# signal_conditioning_circuit.net
KiCad netlist of a schematic drawn in Altium Designer
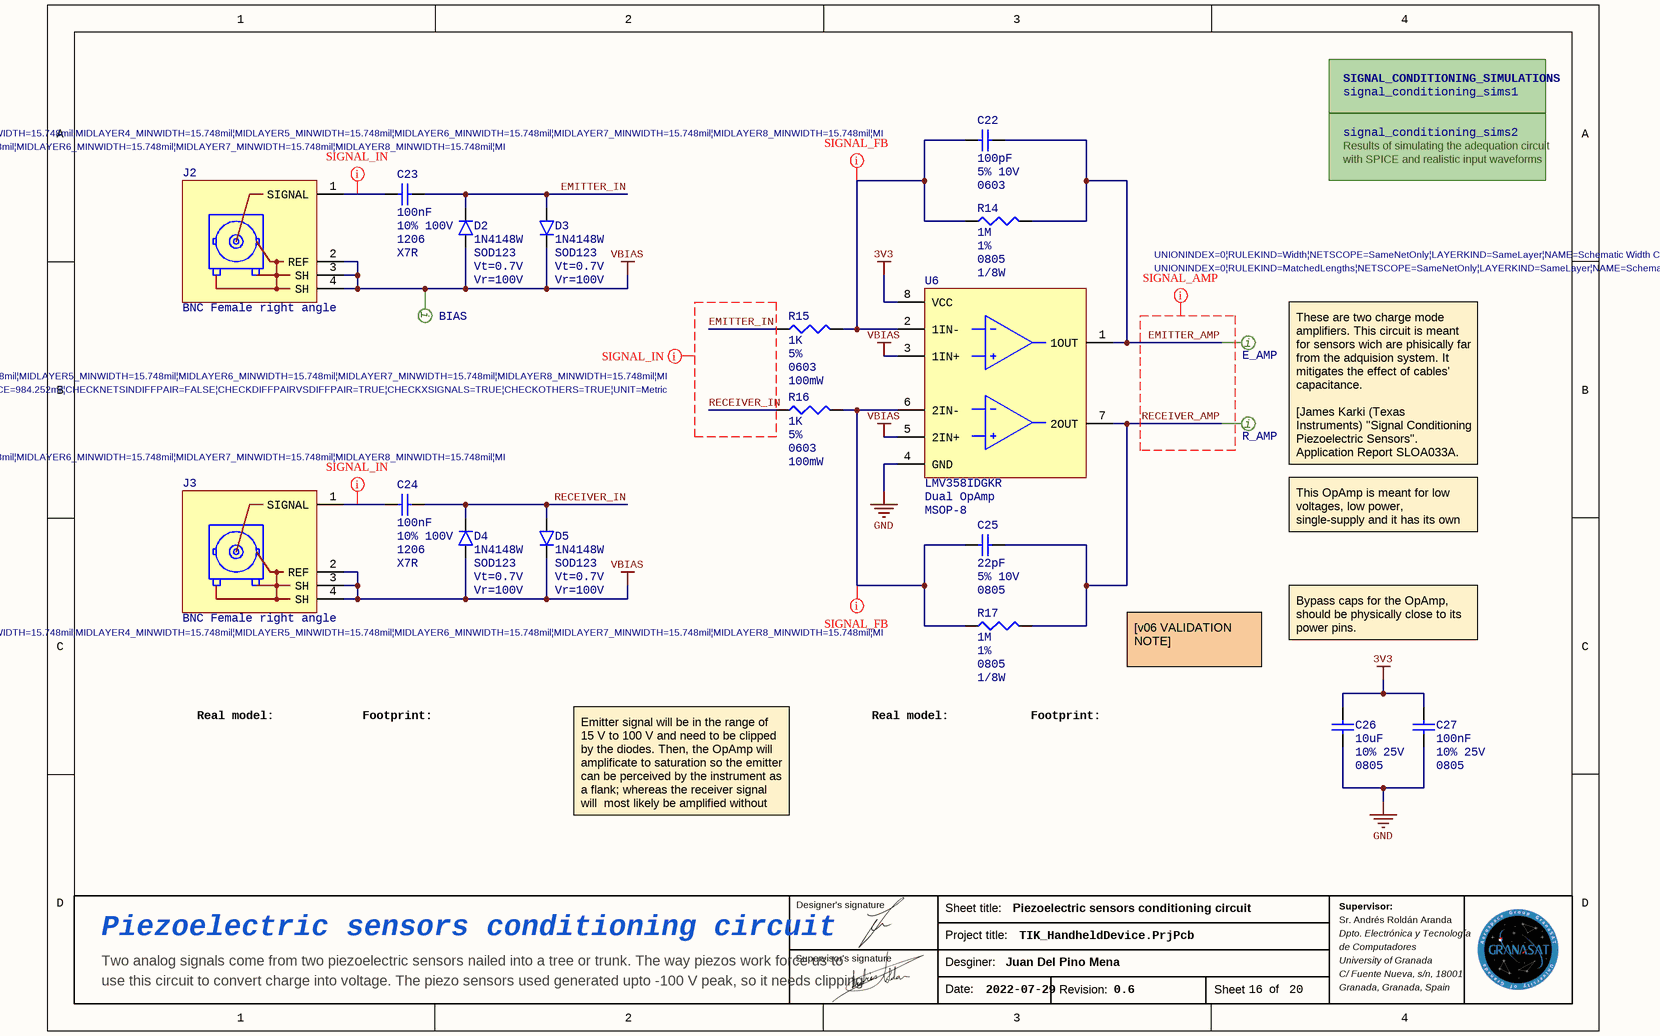
[diagram p0: signal_conditioning_circuit.SchDoc]

(export (version "E")
  (design (tool "Eeschema 10.0.6"))
  (components
    (comp (ref "BIAS")
      (value "Test Point Pad dual sided")
      (footprint "TEST POINT PAD")
      (description "Test point - PCB Pad dual sided")
      (libsource (lib "tik_handheld_schlib") (part "Test Point Pad dual sided"))
    )
    (comp (ref "C22")
      (value "100pF")
      (footprint "CAP 0603_1608")
      (description "Ceramic cap size 0805")
      (fields
        (field (name "TOLERANCE") "5% 10V")
        (field (name "PACKAGEDESCRIPTION") "0603")
        (field (name "Comment") "Cap_cer_0603_100pF_5%")
      )
      (libsource (lib "tik_handheld_schlib") (part "Cap_cer_0603_100pF_5%"))
    )
    (comp (ref "C23")
      (value "100nF")
      (footprint "CAP 1206_3216")
      (description "Ceramic cap size 1206 C1206C104K1RACTU")
      (fields
        (field (name "TOLERANCE") "10% 100V")
        (field (name "PACKAGEDESCRIPTION") "1206")
        (field (name "TYPE") "X7R")
        (field (name "Comment") "Cap_cer_0805")
      )
      (libsource (lib "tik_handheld_schlib") (part "Cap_cer_1206_100nF_100V_10%"))
    )
    (comp (ref "C24")
      (value "100nF")
      (footprint "CAP 1206_3216")
      (description "Ceramic cap size 1206 C1206C104K1RACTU")
      (fields
        (field (name "TOLERANCE") "10% 100V")
        (field (name "PACKAGEDESCRIPTION") "1206")
        (field (name "TYPE") "X7R")
        (field (name "Comment") "Cap_cer_0805")
      )
      (libsource (lib "tik_handheld_schlib") (part "Cap_cer_1206_100nF_100V_10%"))
    )
    (comp (ref "C25")
      (value "22pF")
      (footprint "CAP 0603_1608")
      (description "Ceramic cap size 0805")
      (fields
        (field (name "TOLERANCE") "5% 10V")
        (field (name "PACKAGEDESCRIPTION") "0805")
        (field (name "Comment") "Cap_cer_0603_22pF_5%")
      )
      (libsource (lib "tik_handheld_schlib") (part "Cap_cer_0603_22pF_5%"))
    )
    (comp (ref "C26")
      (value "10uF")
      (footprint "CAP 0805_2012")
      (description "Ceramic cap size 0805")
      (fields
        (field (name "TOLERANCE") "10% 25V")
        (field (name "PACKAGEDESCRIPTION") "0805")
        (field (name "Comment") "Cap_cer_0805")
      )
      (libsource (lib "tik_handheld_schlib") (part "Cap_cer_0805_10uF_10%"))
    )
    (comp (ref "C27")
      (value "100nF")
      (footprint "CAP 0805_2012")
      (description "Ceramic cap size 0805")
      (fields
        (field (name "TOLERANCE") "10% 25V")
        (field (name "PACKAGEDESCRIPTION") "0805")
        (field (name "Comment") "Cap_cer_0805")
      )
      (libsource (lib "tik_handheld_schlib") (part "Cap_cer_0805_100nF_10%"))
    )
    (comp (ref "D2")
      (value "Diode 1N4148W")
      (footprint "SOD123F 1N4148W")
      (description "SURFACE MOUNT FAST SWITCHING DIODE")
      (fields
        (field (name "PART") "1N4148W")
        (field (name "PACKAGEDESCRIPTION") "SOD123")
        (field (name "FORWARDVOLTAGE") "Vt=0.7V")
        (field (name "REVERSEVOLTAGE") "Vr=100V")
      )
      (libsource (lib "tik_handheld_schlib") (part "Diode 1N4148W"))
    )
    (comp (ref "D3")
      (value "Diode 1N4148W")
      (footprint "SOD123F 1N4148W")
      (description "SURFACE MOUNT FAST SWITCHING DIODE")
      (fields
        (field (name "PART") "1N4148W")
        (field (name "PACKAGEDESCRIPTION") "SOD123")
        (field (name "FORWARDVOLTAGE") "Vt=0.7V")
        (field (name "REVERSEVOLTAGE") "Vr=100V")
      )
      (libsource (lib "tik_handheld_schlib") (part "Diode 1N4148W"))
    )
    (comp (ref "D4")
      (value "Diode 1N4148W")
      (footprint "SOD123F 1N4148W")
      (description "SURFACE MOUNT FAST SWITCHING DIODE")
      (fields
        (field (name "PART") "1N4148W")
        (field (name "PACKAGEDESCRIPTION") "SOD123")
        (field (name "FORWARDVOLTAGE") "Vt=0.7V")
        (field (name "REVERSEVOLTAGE") "Vr=100V")
      )
      (libsource (lib "tik_handheld_schlib") (part "Diode 1N4148W"))
    )
    (comp (ref "D5")
      (value "Diode 1N4148W")
      (footprint "SOD123F 1N4148W")
      (description "SURFACE MOUNT FAST SWITCHING DIODE")
      (fields
        (field (name "PART") "1N4148W")
        (field (name "PACKAGEDESCRIPTION") "SOD123")
        (field (name "FORWARDVOLTAGE") "Vt=0.7V")
        (field (name "REVERSEVOLTAGE") "Vr=100V")
      )
      (libsource (lib "tik_handheld_schlib") (part "Diode 1N4148W"))
    )
    (comp (ref "E_AMP")
      (value "Test Point Pad dual sided")
      (footprint "TEST POINT PAD")
      (description "Test point - PCB Pad dual sided")
      (libsource (lib "tik_handheld_schlib") (part "Test Point Pad dual sided"))
    )
    (comp (ref "J2")
      (value "BNC-Female")
      (footprint "BNC RIGHT ANGLE")
      (description "BNC coaxial female connector")
      (fields (field (name "TYPE") "BNC Female right angle"))
      (libsource (lib "tik_handheld_schlib") (part "CON BNC Female Socket"))
    )
    (comp (ref "J3")
      (value "BNC-Female")
      (footprint "BNC RIGHT ANGLE")
      (description "BNC coaxial female connector")
      (fields (field (name "TYPE") "BNC Female right angle"))
      (libsource (lib "tik_handheld_schlib") (part "CON BNC Female Socket"))
    )
    (comp (ref "R14")
      (value "1M")
      (footprint "RES 0805_2012")
      (description "Res size 0805 SMD mounting, low power.\r\nYageo-RC0805FR-071ML")
      (fields
        (field (name "TOLERANCE") "1%")
        (field (name "PACKAGEDESCRIPTION") "0805")
        (field (name "POWERDISIPATED") "1/8W")
        (field (name "Comment") "Yageo-RC0805FR-072ML")
      )
      (libsource (lib "tik_handheld_schlib") (part "Res_0805_1M_1%"))
    )
    (comp (ref "R15")
      (value "1K")
      (footprint "RES 0603_1608")
      (description "Res size 0603 SMD mounting, low power")
      (fields
        (field (name "TOLERANCE") "5%")
        (field (name "PACKAGEDESCRIPTION") "0603")
        (field (name "POWERDISIPATED") "100mW")
        (field (name "Comment") "Res_0603_1K_5%_100mW")
      )
      (libsource (lib "tik_handheld_schlib") (part "Res_0603_1K_5%_100mW"))
    )
    (comp (ref "R16")
      (value "1K")
      (footprint "RES 0603_1608")
      (description "Res size 0603 SMD mounting, low power")
      (fields
        (field (name "TOLERANCE") "5%")
        (field (name "PACKAGEDESCRIPTION") "0603")
        (field (name "POWERDISIPATED") "100mW")
        (field (name "Comment") "Res_0603_1K_5%_100mW")
      )
      (libsource (lib "tik_handheld_schlib") (part "Res_0603_1K_5%_100mW"))
    )
    (comp (ref "R17")
      (value "1M")
      (footprint "RES 0805_2012")
      (description "Res size 0805 SMD mounting, low power.\r\nYageo-RC0805FR-071ML")
      (fields
        (field (name "TOLERANCE") "1%")
        (field (name "PACKAGEDESCRIPTION") "0805")
        (field (name "POWERDISIPATED") "1/8W")
        (field (name "Comment") "Yageo-RC0805FR-072ML")
      )
      (libsource (lib "tik_handheld_schlib") (part "Res_0805_1M_1%"))
    )
    (comp (ref "R_AMP")
      (value "Test Point Pad dual sided")
      (footprint "TEST POINT PAD")
      (description "Test point - PCB Pad dual sided")
      (libsource (lib "tik_handheld_schlib") (part "Test Point Pad dual sided"))
    )
    (comp (ref "U6")
      (value "IC LMV358DGKR OpAmp")
      (footprint "VSSOP-8 DGK (MSOP-8) LMV358")
      (fields
        (field (name "PART") "LMV358IDGKR")
        (field (name "TYPE") "Dual OpAmp")
        (field (name "PACKAGEDESCRIPTION") "MSOP-8")
      )
      (libsource (lib "tik_handheld_schlib") (part "IC LMV358DGKR OpAmp"))
    )
  )
  (nets
    (net (code "1") (name "/EMITTER_AMP") (class "Default")
      (node (ref "C22") (pin "2") (pinfunction "2_2") (pintype "passive"))
      (node (ref "E_AMP") (pin "1") (pinfunction "1_1") (pintype "passive"))
      (node (ref "R14") (pin "2") (pinfunction "2_2") (pintype "passive"))
      (node (ref "U6") (pin "1") (pinfunction "1OUT_1") (pintype "passive"))
    )
    (net (code "2") (name "/EMITTER_IN") (class "Default")
      (node (ref "C23") (pin "2") (pinfunction "2_2") (pintype "passive"))
      (node (ref "D2") (pin "2") (pinfunction "2_2") (pintype "passive"))
      (node (ref "D3") (pin "1") (pinfunction "1_1") (pintype "passive"))
      (node (ref "R15") (pin "1") (pinfunction "1_1") (pintype "passive"))
    )
    (net (code "3") (name "/RECEIVER_AMP") (class "Default")
      (node (ref "C25") (pin "2") (pinfunction "2_2") (pintype "passive"))
      (node (ref "R17") (pin "2") (pinfunction "2_2") (pintype "passive"))
      (node (ref "R_AMP") (pin "1") (pinfunction "1_1") (pintype "passive"))
      (node (ref "U6") (pin "7") (pinfunction "2OUT_7") (pintype "passive"))
    )
    (net (code "4") (name "/RECEIVER_IN") (class "Default")
      (node (ref "C24") (pin "2") (pinfunction "2_2") (pintype "passive"))
      (node (ref "D4") (pin "2") (pinfunction "2_2") (pintype "passive"))
      (node (ref "D5") (pin "1") (pinfunction "1_1") (pintype "passive"))
      (node (ref "R16") (pin "1") (pinfunction "1_1") (pintype "passive"))
    )
    (net (code "5") (name "3V3") (class "Default")
      (node (ref "C26") (pin "2") (pinfunction "2_2") (pintype "passive"))
      (node (ref "C27") (pin "2") (pinfunction "2_2") (pintype "passive"))
      (node (ref "U6") (pin "8") (pinfunction "VCC_8") (pintype "power_in"))
    )
    (net (code "6") (name "GND") (class "Default")
      (node (ref "C26") (pin "1") (pinfunction "1_1") (pintype "passive"))
      (node (ref "C27") (pin "1") (pinfunction "1_1") (pintype "passive"))
      (node (ref "U6") (pin "4") (pinfunction "GND_4") (pintype "power_in"))
    )
    (net (code "7") (name "Net-(J2-SIGNAL)") (class "Default")
      (node (ref "C23") (pin "1") (pinfunction "1_1") (pintype "passive"))
      (node (ref "J2") (pin "1") (pinfunction "SIGNAL_1") (pintype "passive"))
    )
    (net (code "8") (name "Net-(J3-SIGNAL)") (class "Default")
      (node (ref "C24") (pin "1") (pinfunction "1_1") (pintype "passive"))
      (node (ref "J3") (pin "1") (pinfunction "SIGNAL_1") (pintype "passive"))
    )
    (net (code "9") (name "Net-(U6-1IN-)") (class "Default")
      (node (ref "C22") (pin "1") (pinfunction "1_1") (pintype "passive"))
      (node (ref "R14") (pin "1") (pinfunction "1_1") (pintype "passive"))
      (node (ref "R15") (pin "2") (pinfunction "2_2") (pintype "passive"))
      (node (ref "U6") (pin "2") (pinfunction "1IN-_2") (pintype "passive"))
    )
    (net (code "10") (name "Net-(U6-2IN-)") (class "Default")
      (node (ref "C25") (pin "1") (pinfunction "1_1") (pintype "passive"))
      (node (ref "R16") (pin "2") (pinfunction "2_2") (pintype "passive"))
      (node (ref "R17") (pin "1") (pinfunction "1_1") (pintype "passive"))
      (node (ref "U6") (pin "6") (pinfunction "2IN-_6") (pintype "passive"))
    )
    (net (code "11") (name "VBIAS") (class "Default")
      (node (ref "BIAS") (pin "1") (pinfunction "1_1") (pintype "passive"))
      (node (ref "D2") (pin "1") (pinfunction "1_1") (pintype "passive"))
      (node (ref "D3") (pin "2") (pinfunction "2_2") (pintype "passive"))
      (node (ref "D4") (pin "1") (pinfunction "1_1") (pintype "passive"))
      (node (ref "D5") (pin "2") (pinfunction "2_2") (pintype "passive"))
      (node (ref "J2") (pin "2") (pinfunction "REF_2") (pintype "passive"))
      (node (ref "J2") (pin "3") (pinfunction "SH_3") (pintype "passive"))
      (node (ref "J2") (pin "4") (pinfunction "SH_4") (pintype "passive"))
      (node (ref "J3") (pin "2") (pinfunction "REF_2") (pintype "passive"))
      (node (ref "J3") (pin "3") (pinfunction "SH_3") (pintype "passive"))
      (node (ref "J3") (pin "4") (pinfunction "SH_4") (pintype "passive"))
      (node (ref "U6") (pin "3") (pinfunction "1IN+_3") (pintype "passive"))
      (node (ref "U6") (pin "5") (pinfunction "2IN+_5") (pintype "passive"))
    )
  )
)
